# Sheet1.net
KiCad netlist of a schematic drawn in Altium Designer
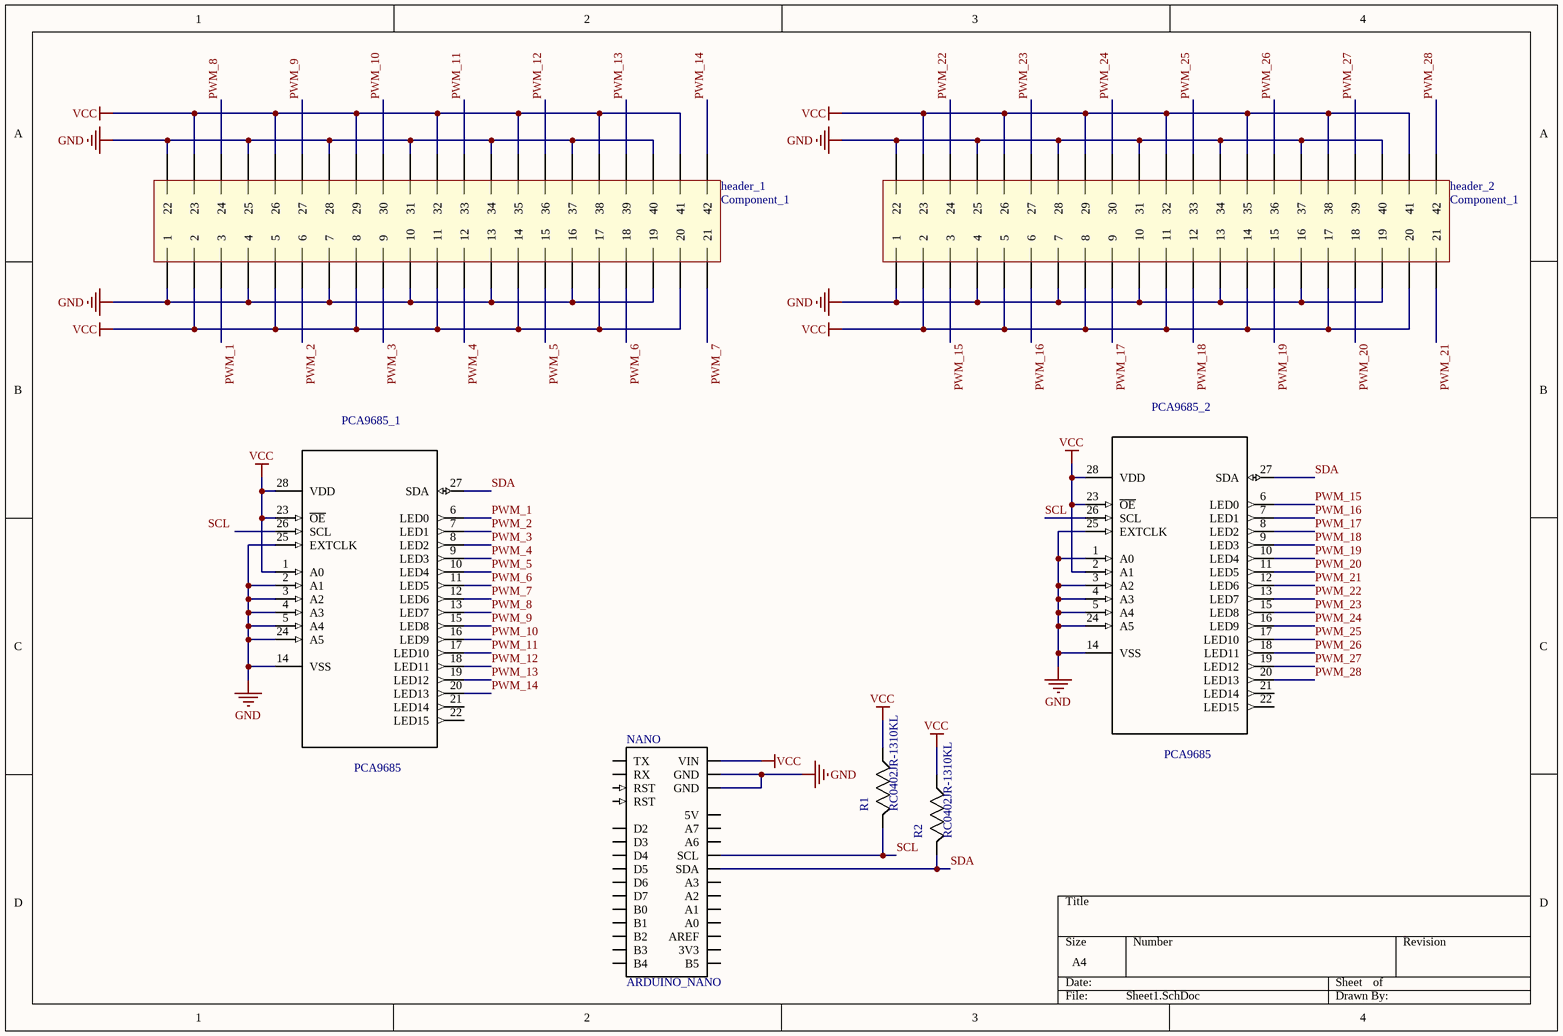
[diagram p0: Sheet1.SchDoc]

(export (version "E")
  (design (tool "Eeschema 10.0.6"))
  (components
    (comp (ref "header_1")
      (value "Component_1")
      (footprint "PCBComponent_1")
      (libsource (lib "Schlib1") (part "Component_1"))
    )
    (comp (ref "header_2")
      (value "Component_1")
      (footprint "PCBComponent_1")
      (libsource (lib "Schlib1") (part "Component_1"))
    )
    (comp (ref "NANO")
      (value "ARDUINO_NANO")
      (footprint "*ARDUINO_NANO")
      (description "Dev.kit: Arduino; UART; ICSP, USB B mini, pin strips")
      (fields (field (name "MF") "Arduino") (field (name "MP") "ARDUINO NANO"))
      (libsource (lib "ARDUINO_NANO") (part "ARDUINO_NANO"))
    )
    (comp (ref "PCA9685_1")
      (value "PCA9685")
      (footprint "*SOP65P640X110-28N")
      (description "PCA9685 Series 5.5V 25 mA 1 MHz 12-bit PWM Fm+I2C-Bus LED Controller - TSSOP-28")
      (fields (field (name "MP") "PCA9685PW,118") (field (name "MF") "NXP USA"))
      (libsource (lib "PCA9685PW_118") (part "PCA9685PW,118"))
    )
    (comp (ref "PCA9685_2")
      (value "PCA9685")
      (footprint "*SOP65P640X110-28N")
      (description "PCA9685 Series 5.5V 25 mA 1 MHz 12-bit PWM Fm+I2C-Bus LED Controller - TSSOP-28")
      (fields (field (name "MP") "PCA9685PW,118") (field (name "MF") "NXP USA"))
      (libsource (lib "PCA9685PW_118") (part "PCA9685PW,118"))
    )
    (comp (ref "R1")
      (value "RC0402JR-1310KL")
      (footprint "*RESC1005X40")
      (description "Res, Thick Film, 10k, 5%, 0.0625w, 0402")
      (fields (field (name "MF") "Yageo"))
      (libsource (lib "RC0402JR-1310KL") (part "RC0402JR-1310KL"))
    )
    (comp (ref "R2")
      (value "RC0402JR-1310KL")
      (footprint "*RESC1005X40")
      (description "Res, Thick Film, 10k, 5%, 0.0625w, 0402")
      (fields (field (name "MF") "Yageo"))
      (libsource (lib "RC0402JR-1310KL") (part "RC0402JR-1310KL"))
    )
  )
  (nets
    (net (code "1") (name "/PWM_1") (class "Default")
      (node (ref "PCA9685_1") (pin "6") (pinfunction "LED0_6") (pintype "output"))
      (node (ref "header_1") (pin "3") (pinfunction "3_3") (pintype "passive"))
    )
    (net (code "2") (name "/PWM_2") (class "Default")
      (node (ref "PCA9685_1") (pin "7") (pinfunction "LED1_7") (pintype "output"))
      (node (ref "header_1") (pin "6") (pinfunction "6_6") (pintype "passive"))
    )
    (net (code "3") (name "/PWM_3") (class "Default")
      (node (ref "PCA9685_1") (pin "8") (pinfunction "LED2_8") (pintype "output"))
      (node (ref "header_1") (pin "9") (pinfunction "9_9") (pintype "passive"))
    )
    (net (code "4") (name "/PWM_4") (class "Default")
      (node (ref "PCA9685_1") (pin "9") (pinfunction "LED3_9") (pintype "output"))
      (node (ref "header_1") (pin "12") (pinfunction "12_12") (pintype "passive"))
    )
    (net (code "5") (name "/PWM_5") (class "Default")
      (node (ref "PCA9685_1") (pin "10") (pinfunction "LED4_10") (pintype "output"))
      (node (ref "header_1") (pin "15") (pinfunction "15_15") (pintype "passive"))
    )
    (net (code "6") (name "/PWM_6") (class "Default")
      (node (ref "PCA9685_1") (pin "11") (pinfunction "LED5_11") (pintype "output"))
      (node (ref "header_1") (pin "18") (pinfunction "18_18") (pintype "passive"))
    )
    (net (code "7") (name "/PWM_7") (class "Default")
      (node (ref "PCA9685_1") (pin "12") (pinfunction "LED6_12") (pintype "output"))
      (node (ref "header_1") (pin "21") (pinfunction "21_21") (pintype "passive"))
    )
    (net (code "8") (name "/PWM_8") (class "Default")
      (node (ref "PCA9685_1") (pin "13") (pinfunction "LED7_13") (pintype "output"))
      (node (ref "header_1") (pin "24") (pinfunction "24_24") (pintype "passive"))
    )
    (net (code "9") (name "/PWM_9") (class "Default")
      (node (ref "PCA9685_1") (pin "15") (pinfunction "LED8_15") (pintype "output"))
      (node (ref "header_1") (pin "27") (pinfunction "27_27") (pintype "passive"))
    )
    (net (code "10") (name "/PWM_10") (class "Default")
      (node (ref "PCA9685_1") (pin "16") (pinfunction "LED9_16") (pintype "output"))
      (node (ref "header_1") (pin "30") (pinfunction "30_30") (pintype "passive"))
    )
    (net (code "11") (name "/PWM_11") (class "Default")
      (node (ref "PCA9685_1") (pin "17") (pinfunction "LED10_17") (pintype "output"))
      (node (ref "header_1") (pin "33") (pinfunction "33_33") (pintype "passive"))
    )
    (net (code "12") (name "/PWM_12") (class "Default")
      (node (ref "PCA9685_1") (pin "18") (pinfunction "LED11_18") (pintype "output"))
      (node (ref "header_1") (pin "36") (pinfunction "36_36") (pintype "passive"))
    )
    (net (code "13") (name "/PWM_13") (class "Default")
      (node (ref "PCA9685_1") (pin "19") (pinfunction "LED12_19") (pintype "output"))
      (node (ref "header_1") (pin "39") (pinfunction "39_39") (pintype "passive"))
    )
    (net (code "14") (name "/PWM_14") (class "Default")
      (node (ref "PCA9685_1") (pin "20") (pinfunction "LED13_20") (pintype "output"))
      (node (ref "header_1") (pin "42") (pinfunction "42_42") (pintype "passive"))
    )
    (net (code "15") (name "/PWM_15") (class "Default")
      (node (ref "PCA9685_2") (pin "6") (pinfunction "LED0_6") (pintype "output"))
      (node (ref "header_2") (pin "3") (pinfunction "3_3") (pintype "passive"))
    )
    (net (code "16") (name "/PWM_16") (class "Default")
      (node (ref "PCA9685_2") (pin "7") (pinfunction "LED1_7") (pintype "output"))
      (node (ref "header_2") (pin "6") (pinfunction "6_6") (pintype "passive"))
    )
    (net (code "17") (name "/PWM_17") (class "Default")
      (node (ref "PCA9685_2") (pin "8") (pinfunction "LED2_8") (pintype "output"))
      (node (ref "header_2") (pin "9") (pinfunction "9_9") (pintype "passive"))
    )
    (net (code "18") (name "/PWM_18") (class "Default")
      (node (ref "PCA9685_2") (pin "9") (pinfunction "LED3_9") (pintype "output"))
      (node (ref "header_2") (pin "12") (pinfunction "12_12") (pintype "passive"))
    )
    (net (code "19") (name "/PWM_19") (class "Default")
      (node (ref "PCA9685_2") (pin "10") (pinfunction "LED4_10") (pintype "output"))
      (node (ref "header_2") (pin "15") (pinfunction "15_15") (pintype "passive"))
    )
    (net (code "20") (name "/PWM_20") (class "Default")
      (node (ref "PCA9685_2") (pin "11") (pinfunction "LED5_11") (pintype "output"))
      (node (ref "header_2") (pin "18") (pinfunction "18_18") (pintype "passive"))
    )
    (net (code "21") (name "/PWM_21") (class "Default")
      (node (ref "PCA9685_2") (pin "12") (pinfunction "LED6_12") (pintype "output"))
      (node (ref "header_2") (pin "21") (pinfunction "21_21") (pintype "passive"))
    )
    (net (code "22") (name "/PWM_22") (class "Default")
      (node (ref "PCA9685_2") (pin "13") (pinfunction "LED7_13") (pintype "output"))
      (node (ref "header_2") (pin "24") (pinfunction "24_24") (pintype "passive"))
    )
    (net (code "23") (name "/PWM_23") (class "Default")
      (node (ref "PCA9685_2") (pin "15") (pinfunction "LED8_15") (pintype "output"))
      (node (ref "header_2") (pin "27") (pinfunction "27_27") (pintype "passive"))
    )
    (net (code "24") (name "/PWM_24") (class "Default")
      (node (ref "PCA9685_2") (pin "16") (pinfunction "LED9_16") (pintype "output"))
      (node (ref "header_2") (pin "30") (pinfunction "30_30") (pintype "passive"))
    )
    (net (code "25") (name "/PWM_25") (class "Default")
      (node (ref "PCA9685_2") (pin "17") (pinfunction "LED10_17") (pintype "output"))
      (node (ref "header_2") (pin "33") (pinfunction "33_33") (pintype "passive"))
    )
    (net (code "26") (name "/PWM_26") (class "Default")
      (node (ref "PCA9685_2") (pin "18") (pinfunction "LED11_18") (pintype "output"))
      (node (ref "header_2") (pin "36") (pinfunction "36_36") (pintype "passive"))
    )
    (net (code "27") (name "/PWM_27") (class "Default")
      (node (ref "PCA9685_2") (pin "19") (pinfunction "LED12_19") (pintype "output"))
      (node (ref "header_2") (pin "39") (pinfunction "39_39") (pintype "passive"))
    )
    (net (code "28") (name "/PWM_28") (class "Default")
      (node (ref "PCA9685_2") (pin "20") (pinfunction "LED13_20") (pintype "output"))
      (node (ref "header_2") (pin "42") (pinfunction "42_42") (pintype "passive"))
    )
    (net (code "29") (name "/SCL") (class "Default")
      (node (ref "NANO") (pin "24") (pinfunction "SCL_24") (pintype "bidirectional"))
      (node (ref "PCA9685_2") (pin "26") (pinfunction "SCL_26") (pintype "input"))
      (node (ref "R1") (pin "1") (pinfunction "1_1") (pintype "passive"))
    )
    (net (code "30") (name "/SDA") (class "Default")
      (node (ref "NANO") (pin "23") (pinfunction "SDA_23") (pintype "bidirectional"))
      (node (ref "PCA9685_1") (pin "27") (pinfunction "SDA_27") (pintype "bidirectional"))
      (node (ref "PCA9685_2") (pin "27") (pinfunction "SDA_27") (pintype "bidirectional"))
      (node (ref "R2") (pin "1") (pinfunction "1_1") (pintype "passive"))
    )
    (net (code "31") (name "GND") (class "Default")
      (node (ref "NANO") (pin "29") (pinfunction "GND_29") (pintype "power_in"))
      (node (ref "NANO") (pin "4") (pinfunction "GND_4") (pintype "power_in"))
      (node (ref "PCA9685_1") (pin "14") (pinfunction "VSS_14") (pintype "passive"))
      (node (ref "PCA9685_1") (pin "2") (pinfunction "A1_2") (pintype "input"))
      (node (ref "PCA9685_1") (pin "24") (pinfunction "A5_24") (pintype "input"))
      (node (ref "PCA9685_1") (pin "25") (pinfunction "EXTCLK_25") (pintype "input"))
      (node (ref "PCA9685_1") (pin "3") (pinfunction "A2_3") (pintype "input"))
      (node (ref "PCA9685_1") (pin "4") (pinfunction "A3_4") (pintype "input"))
      (node (ref "PCA9685_1") (pin "5") (pinfunction "A4_5") (pintype "input"))
      (node (ref "PCA9685_2") (pin "1") (pinfunction "A0_1") (pintype "input"))
      (node (ref "PCA9685_2") (pin "14") (pinfunction "VSS_14") (pintype "passive"))
      (node (ref "PCA9685_2") (pin "24") (pinfunction "A5_24") (pintype "input"))
      (node (ref "PCA9685_2") (pin "25") (pinfunction "EXTCLK_25") (pintype "input"))
      (node (ref "PCA9685_2") (pin "3") (pinfunction "A2_3") (pintype "input"))
      (node (ref "PCA9685_2") (pin "4") (pinfunction "A3_4") (pintype "input"))
      (node (ref "PCA9685_2") (pin "5") (pinfunction "A4_5") (pintype "input"))
      (node (ref "header_1") (pin "1") (pinfunction "1_1") (pintype "passive"))
      (node (ref "header_1") (pin "10") (pinfunction "10_10") (pintype "passive"))
      (node (ref "header_1") (pin "13") (pinfunction "13_13") (pintype "passive"))
      (node (ref "header_1") (pin "16") (pinfunction "16_16") (pintype "passive"))
      (node (ref "header_1") (pin "19") (pinfunction "19_19") (pintype "passive"))
      (node (ref "header_1") (pin "22") (pinfunction "22_22") (pintype "passive"))
      (node (ref "header_1") (pin "25") (pinfunction "25_25") (pintype "passive"))
      (node (ref "header_1") (pin "28") (pinfunction "28_28") (pintype "passive"))
      (node (ref "header_1") (pin "31") (pinfunction "31_31") (pintype "passive"))
      (node (ref "header_1") (pin "34") (pinfunction "34_34") (pintype "passive"))
      (node (ref "header_1") (pin "37") (pinfunction "37_37") (pintype "passive"))
      (node (ref "header_1") (pin "4") (pinfunction "4_4") (pintype "passive"))
      (node (ref "header_1") (pin "40") (pinfunction "40_40") (pintype "passive"))
      (node (ref "header_1") (pin "7") (pinfunction "7_7") (pintype "passive"))
      (node (ref "header_2") (pin "1") (pinfunction "1_1") (pintype "passive"))
      (node (ref "header_2") (pin "10") (pinfunction "10_10") (pintype "passive"))
      (node (ref "header_2") (pin "13") (pinfunction "13_13") (pintype "passive"))
      (node (ref "header_2") (pin "16") (pinfunction "16_16") (pintype "passive"))
      (node (ref "header_2") (pin "19") (pinfunction "19_19") (pintype "passive"))
      (node (ref "header_2") (pin "22") (pinfunction "22_22") (pintype "passive"))
      (node (ref "header_2") (pin "25") (pinfunction "25_25") (pintype "passive"))
      (node (ref "header_2") (pin "28") (pinfunction "28_28") (pintype "passive"))
      (node (ref "header_2") (pin "31") (pinfunction "31_31") (pintype "passive"))
      (node (ref "header_2") (pin "34") (pinfunction "34_34") (pintype "passive"))
      (node (ref "header_2") (pin "37") (pinfunction "37_37") (pintype "passive"))
      (node (ref "header_2") (pin "4") (pinfunction "4_4") (pintype "passive"))
      (node (ref "header_2") (pin "40") (pinfunction "40_40") (pintype "passive"))
      (node (ref "header_2") (pin "7") (pinfunction "7_7") (pintype "passive"))
    )
    (net (code "32") (name "VCC") (class "Default")
      (node (ref "NANO") (pin "30") (pinfunction "VIN_30") (pintype "power_in"))
      (node (ref "PCA9685_1") (pin "1") (pinfunction "A0_1") (pintype "input"))
      (node (ref "PCA9685_1") (pin "23") (pinfunction "~{OE}_23") (pintype "input"))
      (node (ref "PCA9685_1") (pin "28") (pinfunction "VDD_28") (pintype "power_in"))
      (node (ref "PCA9685_2") (pin "2") (pinfunction "A1_2") (pintype "input"))
      (node (ref "PCA9685_2") (pin "23") (pinfunction "~{OE}_23") (pintype "input"))
      (node (ref "PCA9685_2") (pin "28") (pinfunction "VDD_28") (pintype "power_in"))
      (node (ref "R1") (pin "2") (pinfunction "2_2") (pintype "passive"))
      (node (ref "R2") (pin "2") (pinfunction "2_2") (pintype "passive"))
      (node (ref "header_1") (pin "11") (pinfunction "11_11") (pintype "passive"))
      (node (ref "header_1") (pin "14") (pinfunction "14_14") (pintype "passive"))
      (node (ref "header_1") (pin "17") (pinfunction "17_17") (pintype "passive"))
      (node (ref "header_1") (pin "2") (pinfunction "2_2") (pintype "passive"))
      (node (ref "header_1") (pin "20") (pinfunction "20_20") (pintype "passive"))
      (node (ref "header_1") (pin "23") (pinfunction "23_23") (pintype "passive"))
      (node (ref "header_1") (pin "26") (pinfunction "26_26") (pintype "passive"))
      (node (ref "header_1") (pin "29") (pinfunction "29_29") (pintype "passive"))
      (node (ref "header_1") (pin "32") (pinfunction "32_32") (pintype "passive"))
      (node (ref "header_1") (pin "35") (pinfunction "35_35") (pintype "passive"))
      (node (ref "header_1") (pin "38") (pinfunction "38_38") (pintype "passive"))
      (node (ref "header_1") (pin "41") (pinfunction "41_41") (pintype "passive"))
      (node (ref "header_1") (pin "5") (pinfunction "5_5") (pintype "passive"))
      (node (ref "header_1") (pin "8") (pinfunction "8_8") (pintype "passive"))
      (node (ref "header_2") (pin "11") (pinfunction "11_11") (pintype "passive"))
      (node (ref "header_2") (pin "14") (pinfunction "14_14") (pintype "passive"))
      (node (ref "header_2") (pin "17") (pinfunction "17_17") (pintype "passive"))
      (node (ref "header_2") (pin "2") (pinfunction "2_2") (pintype "passive"))
      (node (ref "header_2") (pin "20") (pinfunction "20_20") (pintype "passive"))
      (node (ref "header_2") (pin "23") (pinfunction "23_23") (pintype "passive"))
      (node (ref "header_2") (pin "26") (pinfunction "26_26") (pintype "passive"))
      (node (ref "header_2") (pin "29") (pinfunction "29_29") (pintype "passive"))
      (node (ref "header_2") (pin "32") (pinfunction "32_32") (pintype "passive"))
      (node (ref "header_2") (pin "35") (pinfunction "35_35") (pintype "passive"))
      (node (ref "header_2") (pin "38") (pinfunction "38_38") (pintype "passive"))
      (node (ref "header_2") (pin "41") (pinfunction "41_41") (pintype "passive"))
      (node (ref "header_2") (pin "5") (pinfunction "5_5") (pintype "passive"))
      (node (ref "header_2") (pin "8") (pinfunction "8_8") (pintype "passive"))
    )
    (net (code "33") (name "unconnected-(NANO-3V3-Pad17)") (class "Default")
      (node (ref "NANO") (pin "17") (pinfunction "3V3_17") (pintype "power_in"))
    )
    (net (code "34") (name "unconnected-(NANO-5V-Pad27)") (class "Default")
      (node (ref "NANO") (pin "27") (pinfunction "5V_27") (pintype "power_in"))
    )
    (net (code "35") (name "unconnected-(NANO-A0-Pad19)") (class "Default")
      (node (ref "NANO") (pin "19") (pinfunction "A0_19") (pintype "bidirectional"))
    )
    (net (code "36") (name "unconnected-(NANO-A1-Pad20)") (class "Default")
      (node (ref "NANO") (pin "20") (pinfunction "A1_20") (pintype "bidirectional"))
    )
    (net (code "37") (name "unconnected-(NANO-A2-Pad21)") (class "Default")
      (node (ref "NANO") (pin "21") (pinfunction "A2_21") (pintype "bidirectional"))
    )
    (net (code "38") (name "unconnected-(NANO-A3-Pad22)") (class "Default")
      (node (ref "NANO") (pin "22") (pinfunction "A3_22") (pintype "bidirectional"))
    )
    (net (code "39") (name "unconnected-(NANO-A6-Pad25)") (class "Default")
      (node (ref "NANO") (pin "25") (pinfunction "A6_25") (pintype "bidirectional"))
    )
    (net (code "40") (name "unconnected-(NANO-A7-Pad26)") (class "Default")
      (node (ref "NANO") (pin "26") (pinfunction "A7_26") (pintype "bidirectional"))
    )
    (net (code "41") (name "unconnected-(NANO-AREF-Pad18)") (class "Default")
      (node (ref "NANO") (pin "18") (pinfunction "AREF_18") (pintype "power_in"))
    )
    (net (code "42") (name "unconnected-(NANO-B0-Pad11)") (class "Default")
      (node (ref "NANO") (pin "11") (pinfunction "B0_11") (pintype "bidirectional"))
    )
    (net (code "43") (name "unconnected-(NANO-B1-Pad12)") (class "Default")
      (node (ref "NANO") (pin "12") (pinfunction "B1_12") (pintype "bidirectional"))
    )
    (net (code "44") (name "unconnected-(NANO-B2-Pad13)") (class "Default")
      (node (ref "NANO") (pin "13") (pinfunction "B2_13") (pintype "bidirectional"))
    )
    (net (code "45") (name "unconnected-(NANO-B3-Pad14)") (class "Default")
      (node (ref "NANO") (pin "14") (pinfunction "B3_14") (pintype "bidirectional"))
    )
    (net (code "46") (name "unconnected-(NANO-B4-Pad15)") (class "Default")
      (node (ref "NANO") (pin "15") (pinfunction "B4_15") (pintype "bidirectional"))
    )
    (net (code "47") (name "unconnected-(NANO-B5-Pad16)") (class "Default")
      (node (ref "NANO") (pin "16") (pinfunction "B5_16") (pintype "bidirectional"))
    )
    (net (code "48") (name "unconnected-(NANO-D2-Pad5)") (class "Default")
      (node (ref "NANO") (pin "5") (pinfunction "D2_5") (pintype "bidirectional"))
    )
    (net (code "49") (name "unconnected-(NANO-D3-Pad6)") (class "Default")
      (node (ref "NANO") (pin "6") (pinfunction "D3_6") (pintype "bidirectional"))
    )
    (net (code "50") (name "unconnected-(NANO-D4-Pad7)") (class "Default")
      (node (ref "NANO") (pin "7") (pinfunction "D4_7") (pintype "bidirectional"))
    )
    (net (code "51") (name "unconnected-(NANO-D5-Pad8)") (class "Default")
      (node (ref "NANO") (pin "8") (pinfunction "D5_8") (pintype "bidirectional"))
    )
    (net (code "52") (name "unconnected-(NANO-D6-Pad9)") (class "Default")
      (node (ref "NANO") (pin "9") (pinfunction "D6_9") (pintype "bidirectional"))
    )
    (net (code "53") (name "unconnected-(NANO-D7-Pad10)") (class "Default")
      (node (ref "NANO") (pin "10") (pinfunction "D7_10") (pintype "bidirectional"))
    )
    (net (code "54") (name "unconnected-(NANO-RST-Pad3)") (class "Default")
      (node (ref "NANO") (pin "3") (pinfunction "RST_3") (pintype "input"))
    )
    (net (code "55") (name "unconnected-(NANO-RST-Pad28)") (class "Default")
      (node (ref "NANO") (pin "28") (pinfunction "RST_28") (pintype "input"))
    )
    (net (code "56") (name "unconnected-(NANO-RX-Pad2)") (class "Default")
      (node (ref "NANO") (pin "2") (pinfunction "RX_2") (pintype "bidirectional"))
    )
    (net (code "57") (name "unconnected-(NANO-TX-Pad1)") (class "Default")
      (node (ref "NANO") (pin "1") (pinfunction "TX_1") (pintype "bidirectional"))
    )
    (net (code "58") (name "unconnected-(PCA9685_1-LED14-Pad21)") (class "Default")
      (node (ref "PCA9685_1") (pin "21") (pinfunction "LED14_21") (pintype "output"))
    )
    (net (code "59") (name "unconnected-(PCA9685_1-LED15-Pad22)") (class "Default")
      (node (ref "PCA9685_1") (pin "22") (pinfunction "LED15_22") (pintype "output"))
    )
    (net (code "60") (name "unconnected-(PCA9685_1-SCL-Pad26)") (class "Default")
      (node (ref "PCA9685_1") (pin "26") (pinfunction "SCL_26") (pintype "input"))
    )
    (net (code "61") (name "unconnected-(PCA9685_2-LED14-Pad21)") (class "Default")
      (node (ref "PCA9685_2") (pin "21") (pinfunction "LED14_21") (pintype "output"))
    )
    (net (code "62") (name "unconnected-(PCA9685_2-LED15-Pad22)") (class "Default")
      (node (ref "PCA9685_2") (pin "22") (pinfunction "LED15_22") (pintype "output"))
    )
  )
)
